# dintervalometer.net
KiCad netlist of a schematic drawn in EAGLE
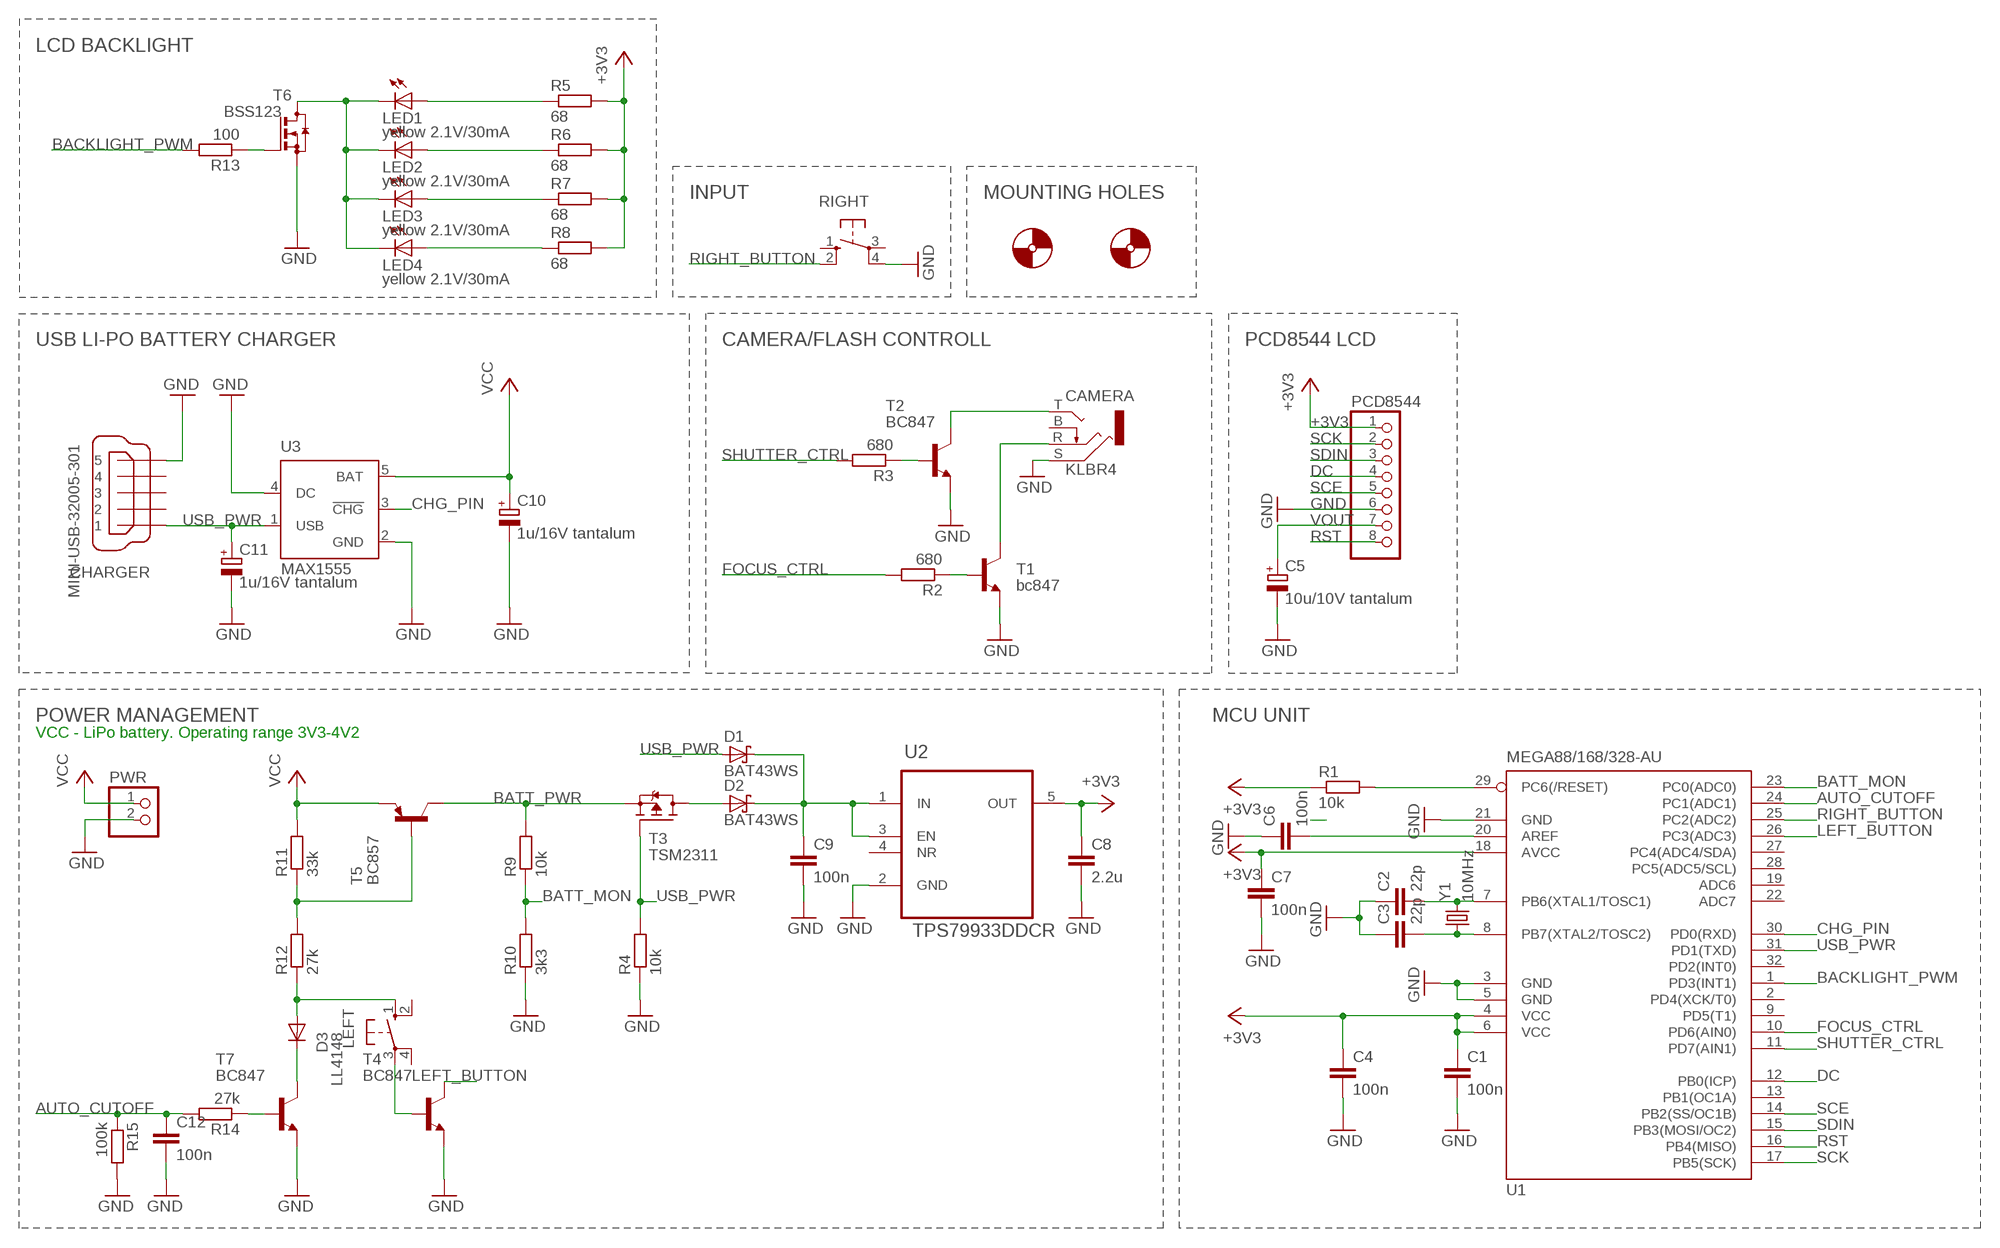
[diagram p0: schematic, sheet 1]

(export (version "E")
  (design (tool "Eeschema 10.0.6"))
  (components
    (comp (ref "C1")
      (value "100n")
      (footprint "eagle-import:C0805")
      (libsource (lib "eagle-import") (part "C-EUC0805"))
    )
    (comp (ref "C2")
      (value "22p")
      (footprint "eagle-import:C0805")
      (libsource (lib "eagle-import") (part "C-EUC0805"))
    )
    (comp (ref "C3")
      (value "22p")
      (footprint "eagle-import:C0805")
      (libsource (lib "eagle-import") (part "C-EUC0805"))
    )
    (comp (ref "C4")
      (value "100n")
      (footprint "eagle-import:C0805")
      (libsource (lib "eagle-import") (part "C-EUC0805"))
    )
    (comp (ref "C5")
      (value "10u/10V tantalum")
      (footprint "eagle-import:SMC_A")
      (libsource (lib "eagle-import") (part "CPOL-EUSMCA"))
    )
    (comp (ref "C6")
      (value "100n")
      (footprint "eagle-import:C0805")
      (libsource (lib "eagle-import") (part "C-EUC0805"))
    )
    (comp (ref "C7")
      (value "100n")
      (footprint "eagle-import:C0805")
      (libsource (lib "eagle-import") (part "C-EUC0805"))
    )
    (comp (ref "C8")
      (value "2.2u")
      (footprint "eagle-import:C0805")
      (libsource (lib "eagle-import") (part "C-EUC0805"))
    )
    (comp (ref "C9")
      (value "100n")
      (footprint "eagle-import:C0805")
      (libsource (lib "eagle-import") (part "C-EUC0805"))
    )
    (comp (ref "C10")
      (value "1u/16V tantalum")
      (footprint "eagle-import:SMC_A")
      (libsource (lib "eagle-import") (part "CPOL-EUSMCA"))
    )
    (comp (ref "C11")
      (value "1u/16V tantalum")
      (footprint "eagle-import:SMC_A")
      (libsource (lib "eagle-import") (part "CPOL-EUSMCA"))
    )
    (comp (ref "C12")
      (value "100n")
      (footprint "eagle-import:C0805")
      (libsource (lib "eagle-import") (part "C-EUC0805"))
    )
    (comp (ref "CAMERA")
      (value "KLBR4")
      (footprint "eagle-import:KLBR4")
      (fields (field (name "MPN") "KLBR 4"))
      (libsource (lib "eagle-import") (part "KLBR4"))
    )
    (comp (ref "CHARGER")
      (value "MINI-USB-32005-301")
      (footprint "eagle-import:32005-301")
      (libsource (lib "eagle-import") (part "MINI-USB-32005-301"))
    )
    (comp (ref "D1")
      (value "BAT43WS")
      (footprint "eagle-import:SOD323_ST")
      (libsource (lib "eagle-import") (part "BAT43WS"))
    )
    (comp (ref "D2")
      (value "BAT43WS")
      (footprint "eagle-import:SOD323_ST")
      (libsource (lib "eagle-import") (part "BAT43WS"))
    )
    (comp (ref "D3")
      (value "LL4148")
      (footprint "eagle-import:SOD80C")
      (libsource (lib "eagle-import") (part "DIODE-SOD80C"))
    )
    (comp (ref "LED1")
      (value "yellow 2.1V/30mA")
      (footprint "eagle-import:CHIP-LED0805")
      (libsource (lib "eagle-import") (part "LEDCHIP-LED0805"))
    )
    (comp (ref "LED2")
      (value "yellow 2.1V/30mA")
      (footprint "eagle-import:CHIP-LED0805")
      (libsource (lib "eagle-import") (part "LEDCHIP-LED0805"))
    )
    (comp (ref "LED3")
      (value "yellow 2.1V/30mA")
      (footprint "eagle-import:CHIP-LED0805")
      (libsource (lib "eagle-import") (part "LEDCHIP-LED0805"))
    )
    (comp (ref "LED4")
      (value "yellow 2.1V/30mA")
      (footprint "eagle-import:CHIP-LED0805")
      (libsource (lib "eagle-import") (part "LEDCHIP-LED0805"))
    )
    (comp (ref "LEFT")
      (value "10-XX")
      (footprint "eagle-import:B3F-10XX")
      (fields (field (name "MPN") "B3F-1000"))
      (libsource (lib "eagle-import") (part "10-XX"))
    )
    (comp (ref "PCD8544")
      (value "PINHD-1X8")
      (footprint "eagle-import:1X08")
      (libsource (lib "eagle-import") (part "PINHD-1X8"))
    )
    (comp (ref "PWR")
      (value "PINHD-1X2/90")
      (footprint "eagle-import:1X02_90")
      (libsource (lib "eagle-import") (part "PINHD-1X2/90"))
    )
    (comp (ref "R1")
      (value "10k")
      (footprint "eagle-import:M0805")
      (libsource (lib "eagle-import") (part "R-EU_M0805"))
    )
    (comp (ref "R2")
      (value "680")
      (footprint "eagle-import:M0805")
      (libsource (lib "eagle-import") (part "R-EU_M0805"))
    )
    (comp (ref "R3")
      (value "680")
      (footprint "eagle-import:M0805")
      (libsource (lib "eagle-import") (part "R-EU_M0805"))
    )
    (comp (ref "R4")
      (value "10k")
      (footprint "eagle-import:M0805")
      (libsource (lib "eagle-import") (part "R-EU_M0805"))
    )
    (comp (ref "R5")
      (value "68")
      (footprint "eagle-import:M0805")
      (libsource (lib "eagle-import") (part "R-EU_M0805"))
    )
    (comp (ref "R6")
      (value "68")
      (footprint "eagle-import:M0805")
      (libsource (lib "eagle-import") (part "R-EU_M0805"))
    )
    (comp (ref "R7")
      (value "68")
      (footprint "eagle-import:M0805")
      (libsource (lib "eagle-import") (part "R-EU_M0805"))
    )
    (comp (ref "R8")
      (value "68")
      (footprint "eagle-import:M0805")
      (libsource (lib "eagle-import") (part "R-EU_M0805"))
    )
    (comp (ref "R9")
      (value "10k")
      (footprint "eagle-import:M0805")
      (libsource (lib "eagle-import") (part "R-EU_M0805"))
    )
    (comp (ref "R10")
      (value "3k3")
      (footprint "eagle-import:M0805")
      (libsource (lib "eagle-import") (part "R-EU_M0805"))
    )
    (comp (ref "R11")
      (value "33k")
      (footprint "eagle-import:M0805")
      (libsource (lib "eagle-import") (part "R-EU_M0805"))
    )
    (comp (ref "R12")
      (value "27k")
      (footprint "eagle-import:M0805")
      (libsource (lib "eagle-import") (part "R-EU_M0805"))
    )
    (comp (ref "R13")
      (value "100")
      (footprint "eagle-import:M0805")
      (libsource (lib "eagle-import") (part "R-EU_M0805"))
    )
    (comp (ref "R14")
      (value "27k")
      (footprint "eagle-import:M0805")
      (libsource (lib "eagle-import") (part "R-EU_M0805"))
    )
    (comp (ref "R15")
      (value "100k")
      (footprint "eagle-import:M0805")
      (libsource (lib "eagle-import") (part "R-EU_M0805"))
    )
    (comp (ref "RIGHT")
      (value "10-XX")
      (footprint "eagle-import:B3F-10XX")
      (fields
        (field (name "MPN") "B3F-1000")
        (field (name "MPN_1") "B3F-1000")
        (field (name "OC_FARNELL") "176432")
        (field (name "OC_NEWARK") "36M3542")
      )
      (libsource (lib "eagle-import") (part "10-XX"))
    )
    (comp (ref "T1")
      (value "bc847")
      (footprint "eagle-import:SOT23-BEC")
      (libsource (lib "eagle-import") (part "-NPN-SOT23-BECBC847"))
    )
    (comp (ref "T2")
      (value "BC847")
      (footprint "eagle-import:SOT23-BEC")
      (libsource (lib "eagle-import") (part "-NPN-SOT23-BECBC847"))
    )
    (comp (ref "T3")
      (value "TSM2311")
      (footprint "eagle-import:SOT23")
      (libsource (lib "eagle-import") (part "TSM2311"))
    )
    (comp (ref "T4")
      (value "BC847")
      (footprint "eagle-import:SOT23")
      (libsource (lib "eagle-import") (part "BC847"))
    )
    (comp (ref "T5")
      (value "BC857")
      (footprint "eagle-import:SOT23-BEC")
      (libsource (lib "eagle-import") (part "-PNP-SOT23-BECBC857A"))
    )
    (comp (ref "T6")
      (value "BSS123")
      (footprint "eagle-import:SOT23")
      (libsource (lib "eagle-import") (part "BSS123"))
    )
    (comp (ref "T7")
      (value "BC847")
      (footprint "eagle-import:SOT23")
      (libsource (lib "eagle-import") (part "BC847"))
    )
    (comp (ref "U1")
      (value "MEGA88/168/328-AU")
      (footprint "eagle-import:TQFP32-08")
      (fields (field (name "MPN") "ATMEGA8-16AU"))
      (libsource (lib "eagle-import") (part "MEGA8-AI"))
    )
    (comp (ref "U2")
      (value "TPS79933DDCR")
      (footprint "eagle-import:SOT95P290X145-5N")
      (fields (field (name "MPN") "TPS73033DBVT"))
      (libsource (lib "eagle-import") (part "TPS73033DBVT"))
    )
    (comp (ref "U3")
      (value "MAX1555")
      (footprint "eagle-import:SOT23-5L")
      (fields (field (name "MF") "MAXIM") (field (name "MPN") "MAX1555EZK+T"))
      (libsource (lib "eagle-import") (part "MAX1555"))
    )
    (comp (ref "X1")
      (value "2.8MM_HOLE")
      (footprint "eagle-import:2.8MM_HOLE")
      (libsource (lib "eagle-import") (part "2.8MM_HOLE"))
    )
    (comp (ref "X3")
      (value "2.8MM_HOLE")
      (footprint "eagle-import:2.8MM_HOLE")
      (libsource (lib "eagle-import") (part "2.8MM_HOLE"))
    )
    (comp (ref "Y1")
      (value "10MHz")
      (footprint "eagle-import:5X3.2MM")
      (libsource (lib "eagle-import") (part "CRYSTAL"))
    )
  )
  (nets
    (net (code "1") (name "+3V3") (class "Default")
      (node (ref "C1") (pin "1") (pinfunction "1_1") (pintype "passive"))
      (node (ref "C4") (pin "1") (pinfunction "1_1") (pintype "passive"))
      (node (ref "C7") (pin "1") (pinfunction "1_1") (pintype "passive"))
      (node (ref "C8") (pin "1") (pinfunction "1_1") (pintype "passive"))
      (node (ref "PCD8544") (pin "1") (pinfunction "1_1") (pintype "passive"))
      (node (ref "R1") (pin "1") (pinfunction "1_1") (pintype "passive"))
      (node (ref "R5") (pin "2") (pinfunction "2_2") (pintype "passive"))
      (node (ref "R6") (pin "2") (pinfunction "2_2") (pintype "passive"))
      (node (ref "R7") (pin "2") (pinfunction "2_2") (pintype "passive"))
      (node (ref "R8") (pin "2") (pinfunction "2_2") (pintype "passive"))
      (node (ref "U1") (pin "18") (pinfunction "AVCC_18") (pintype "power_in"))
      (node (ref "U1") (pin "4") (pinfunction "VCC_4") (pintype "power_in"))
      (node (ref "U1") (pin "6") (pinfunction "VCC_6") (pintype "power_in"))
      (node (ref "U2") (pin "5") (pinfunction "OUT_5") (pintype "output"))
    )
    (net (code "2") (name "/AUTO_CUTOFF") (class "Default")
      (node (ref "C12") (pin "1") (pinfunction "1_1") (pintype "passive"))
      (node (ref "R14") (pin "2") (pinfunction "2_2") (pintype "passive"))
      (node (ref "R15") (pin "1") (pinfunction "1_1") (pintype "passive"))
      (node (ref "U1") (pin "24") (pinfunction "PC1(ADC1)_24") (pintype "bidirectional"))
    )
    (net (code "3") (name "/BACKLIGHT_PWM") (class "Default")
      (node (ref "R13") (pin "2") (pinfunction "2_2") (pintype "passive"))
      (node (ref "U1") (pin "1") (pinfunction "PD3(INT1)_1") (pintype "bidirectional"))
    )
    (net (code "4") (name "/BATT_MON") (class "Default")
      (node (ref "R10") (pin "2") (pinfunction "2_2") (pintype "passive"))
      (node (ref "R9") (pin "1") (pinfunction "1_1") (pintype "passive"))
      (node (ref "U1") (pin "23") (pinfunction "PC0(ADC0)_23") (pintype "bidirectional"))
    )
    (net (code "5") (name "/BATT_PWR") (class "Default")
      (node (ref "R9") (pin "2") (pinfunction "2_2") (pintype "passive"))
      (node (ref "T3") (pin "2") (pinfunction "S_2") (pintype "passive"))
      (node (ref "T5") (pin "C") (pinfunction "C_C") (pintype "passive"))
    )
    (net (code "6") (name "/CHG_PIN") (class "Default")
      (node (ref "U1") (pin "30") (pinfunction "PD0(RXD)_30") (pintype "bidirectional"))
      (node (ref "U3") (pin "3") (pinfunction "~{CHG}_3") (pintype "output"))
    )
    (net (code "7") (name "/DC") (class "Default")
      (node (ref "PCD8544") (pin "4") (pinfunction "4_4") (pintype "passive"))
      (node (ref "U1") (pin "12") (pinfunction "PB0(ICP)_12") (pintype "bidirectional"))
    )
    (net (code "8") (name "/FOCUS_CTRL") (class "Default")
      (node (ref "R2") (pin "2") (pinfunction "2_2") (pintype "passive"))
      (node (ref "U1") (pin "10") (pinfunction "PD6(AIN0)_10") (pintype "bidirectional"))
    )
    (net (code "9") (name "/LEFT_BUTTON") (class "Default")
      (node (ref "T4") (pin "3") (pinfunction "C_3") (pintype "passive"))
      (node (ref "U1") (pin "26") (pinfunction "PC3(ADC3)_26") (pintype "bidirectional"))
    )
    (net (code "10") (name "/RIGHT_BUTTON") (class "Default")
      (node (ref "RIGHT") (pin "2") (pinfunction "S1_2") (pintype "passive"))
      (node (ref "U1") (pin "25") (pinfunction "PC2(ADC2)_25") (pintype "bidirectional"))
    )
    (net (code "11") (name "/RST") (class "Default")
      (node (ref "PCD8544") (pin "8") (pinfunction "8_8") (pintype "passive"))
      (node (ref "U1") (pin "16") (pinfunction "PB4(MISO)_16") (pintype "bidirectional"))
    )
    (net (code "12") (name "/SCE") (class "Default")
      (node (ref "PCD8544") (pin "5") (pinfunction "5_5") (pintype "passive"))
      (node (ref "U1") (pin "14") (pinfunction "PB2(SS/OC1B)_14") (pintype "bidirectional"))
    )
    (net (code "13") (name "/SCK") (class "Default")
      (node (ref "PCD8544") (pin "2") (pinfunction "2_2") (pintype "passive"))
      (node (ref "U1") (pin "17") (pinfunction "PB5(SCK)_17") (pintype "bidirectional"))
    )
    (net (code "14") (name "/SDIN") (class "Default")
      (node (ref "PCD8544") (pin "3") (pinfunction "3_3") (pintype "passive"))
      (node (ref "U1") (pin "15") (pinfunction "PB3(MOSI/OC2)_15") (pintype "bidirectional"))
    )
    (net (code "15") (name "/SHUTTER_CTRL") (class "Default")
      (node (ref "R3") (pin "2") (pinfunction "2_2") (pintype "passive"))
      (node (ref "U1") (pin "11") (pinfunction "PD7(AIN1)_11") (pintype "bidirectional"))
    )
    (net (code "16") (name "/USB_PWR") (class "Default")
      (node (ref "C11") (pin "+") (pinfunction "+_+") (pintype "passive"))
      (node (ref "CHARGER") (pin "1") (pinfunction "1_1") (pintype "passive"))
      (node (ref "D1") (pin "A") (pinfunction "A_A") (pintype "passive"))
      (node (ref "R4") (pin "2") (pinfunction "2_2") (pintype "passive"))
      (node (ref "T3") (pin "1") (pinfunction "G_1") (pintype "passive"))
      (node (ref "U1") (pin "31") (pinfunction "PD1(TXD)_31") (pintype "bidirectional"))
      (node (ref "U3") (pin "1") (pinfunction "USB_1") (pintype "input"))
    )
    (net (code "17") (name "/VOUT") (class "Default")
      (node (ref "C5") (pin "+") (pinfunction "+_+") (pintype "passive"))
      (node (ref "PCD8544") (pin "7") (pinfunction "7_7") (pintype "passive"))
    )
    (net (code "18") (name "GND") (class "Default")
      (node (ref "C1") (pin "2") (pinfunction "2_2") (pintype "passive"))
      (node (ref "C10") (pin "-") (pinfunction "-_-") (pintype "passive"))
      (node (ref "C11") (pin "-") (pinfunction "-_-") (pintype "passive"))
      (node (ref "C12") (pin "2") (pinfunction "2_2") (pintype "passive"))
      (node (ref "C2") (pin "1") (pinfunction "1_1") (pintype "passive"))
      (node (ref "C3") (pin "1") (pinfunction "1_1") (pintype "passive"))
      (node (ref "C4") (pin "2") (pinfunction "2_2") (pintype "passive"))
      (node (ref "C5") (pin "-") (pinfunction "-_-") (pintype "passive"))
      (node (ref "C6") (pin "1") (pinfunction "1_1") (pintype "passive"))
      (node (ref "C7") (pin "2") (pinfunction "2_2") (pintype "passive"))
      (node (ref "C8") (pin "2") (pinfunction "2_2") (pintype "passive"))
      (node (ref "C9") (pin "2") (pinfunction "2_2") (pintype "passive"))
      (node (ref "CAMERA") (pin "S") (pinfunction "S_S") (pintype "passive"))
      (node (ref "CHARGER") (pin "5") (pinfunction "5_5") (pintype "passive"))
      (node (ref "PCD8544") (pin "6") (pinfunction "6_6") (pintype "passive"))
      (node (ref "PWR") (pin "2") (pinfunction "2_2") (pintype "passive"))
      (node (ref "R10") (pin "1") (pinfunction "1_1") (pintype "passive"))
      (node (ref "R15") (pin "2") (pinfunction "2_2") (pintype "passive"))
      (node (ref "R4") (pin "1") (pinfunction "1_1") (pintype "passive"))
      (node (ref "RIGHT") (pin "4") (pinfunction "P1_4") (pintype "passive"))
      (node (ref "T1") (pin "E") (pinfunction "E_E") (pintype "passive"))
      (node (ref "T2") (pin "E") (pinfunction "E_E") (pintype "passive"))
      (node (ref "T4") (pin "2") (pinfunction "E_2") (pintype "passive"))
      (node (ref "T6") (pin "2") (pinfunction "S_2") (pintype "passive"))
      (node (ref "T7") (pin "2") (pinfunction "E_2") (pintype "passive"))
      (node (ref "U1") (pin "21") (pinfunction "GND_21") (pintype "power_in"))
      (node (ref "U1") (pin "3") (pinfunction "GND_3") (pintype "power_in"))
      (node (ref "U1") (pin "5") (pinfunction "GND_5") (pintype "power_in"))
      (node (ref "U2") (pin "2") (pinfunction "GND_2") (pintype "passive"))
      (node (ref "U3") (pin "2") (pinfunction "GND_2") (pintype "power_in"))
      (node (ref "U3") (pin "4") (pinfunction "DC_4") (pintype "input"))
    )
    (net (code "19") (name "Net-(CAMERA-PadR)") (class "Default")
      (node (ref "CAMERA") (pin "R") (pinfunction "R_R") (pintype "passive"))
      (node (ref "T1") (pin "C") (pinfunction "C_C") (pintype "passive"))
    )
    (net (code "20") (name "Net-(CAMERA-PadT)") (class "Default")
      (node (ref "CAMERA") (pin "T") (pinfunction "T_T") (pintype "passive"))
      (node (ref "T2") (pin "C") (pinfunction "C_C") (pintype "passive"))
    )
    (net (code "21") (name "Net-(LED1-PadA)") (class "Default")
      (node (ref "LED1") (pin "A") (pinfunction "A_A") (pintype "passive"))
      (node (ref "R5") (pin "1") (pinfunction "1_1") (pintype "passive"))
    )
    (net (code "22") (name "Net-(LED2-PadA)") (class "Default")
      (node (ref "LED2") (pin "A") (pinfunction "A_A") (pintype "passive"))
      (node (ref "R6") (pin "1") (pinfunction "1_1") (pintype "passive"))
    )
    (net (code "23") (name "Net-(LED3-PadA)") (class "Default")
      (node (ref "LED3") (pin "A") (pinfunction "A_A") (pintype "passive"))
      (node (ref "R7") (pin "1") (pinfunction "1_1") (pintype "passive"))
    )
    (net (code "24") (name "Net-(LED4-PadA)") (class "Default")
      (node (ref "LED4") (pin "A") (pinfunction "A_A") (pintype "passive"))
      (node (ref "R8") (pin "1") (pinfunction "1_1") (pintype "passive"))
    )
    (net (code "25") (name "Net-(LEFT-P)") (class "Default")
      (node (ref "LEFT") (pin "3") (pinfunction "P_3") (pintype "passive"))
      (node (ref "T4") (pin "1") (pinfunction "B_1") (pintype "passive"))
    )
    (net (code "26") (name "Net-(LEFT-S)") (class "Default")
      (node (ref "D3") (pin "A") (pinfunction "A_A") (pintype "passive"))
      (node (ref "LEFT") (pin "1") (pinfunction "S_1") (pintype "passive"))
      (node (ref "R12") (pin "1") (pinfunction "1_1") (pintype "passive"))
    )
    (net (code "27") (name "Net-(R2-Pad1)") (class "Default")
      (node (ref "R2") (pin "1") (pinfunction "1_1") (pintype "passive"))
      (node (ref "T1") (pin "B") (pinfunction "B_B") (pintype "passive"))
    )
    (net (code "28") (name "Net-(R3-Pad1)") (class "Default")
      (node (ref "R3") (pin "1") (pinfunction "1_1") (pintype "passive"))
      (node (ref "T2") (pin "B") (pinfunction "B_B") (pintype "passive"))
    )
    (net (code "29") (name "Net-(R11-Pad1)") (class "Default")
      (node (ref "R11") (pin "1") (pinfunction "1_1") (pintype "passive"))
      (node (ref "R12") (pin "2") (pinfunction "2_2") (pintype "passive"))
      (node (ref "T5") (pin "B") (pinfunction "B_B") (pintype "passive"))
    )
    (net (code "30") (name "Net-(T3-D)") (class "Default")
      (node (ref "D2") (pin "A") (pinfunction "A_A") (pintype "passive"))
      (node (ref "T3") (pin "3") (pinfunction "D_3") (pintype "passive"))
    )
    (net (code "31") (name "Net-(T6-D)") (class "Default")
      (node (ref "LED1") (pin "C") (pinfunction "C_C") (pintype "passive"))
      (node (ref "LED2") (pin "C") (pinfunction "C_C") (pintype "passive"))
      (node (ref "LED3") (pin "C") (pinfunction "C_C") (pintype "passive"))
      (node (ref "LED4") (pin "C") (pinfunction "C_C") (pintype "passive"))
      (node (ref "T6") (pin "3") (pinfunction "D_3") (pintype "passive"))
    )
    (net (code "32") (name "Net-(T6-G)") (class "Default")
      (node (ref "R13") (pin "1") (pinfunction "1_1") (pintype "passive"))
      (node (ref "T6") (pin "1") (pinfunction "G_1") (pintype "passive"))
    )
    (net (code "33") (name "Net-(T7-B)") (class "Default")
      (node (ref "R14") (pin "1") (pinfunction "1_1") (pintype "passive"))
      (node (ref "T7") (pin "1") (pinfunction "B_1") (pintype "passive"))
    )
    (net (code "34") (name "Net-(T7-C)") (class "Default")
      (node (ref "D3") (pin "C") (pinfunction "C_C") (pintype "passive"))
      (node (ref "T7") (pin "3") (pinfunction "C_3") (pintype "passive"))
    )
    (net (code "35") (name "Net-(U1-AREF)") (class "Default")
      (node (ref "C6") (pin "2") (pinfunction "2_2") (pintype "passive"))
      (node (ref "U1") (pin "20") (pinfunction "AREF_20") (pintype "passive"))
    )
    (net (code "36") (name "Net-(U1-PB6(XTAL1{slash}TOSC1))") (class "Default")
      (node (ref "C2") (pin "2") (pinfunction "2_2") (pintype "passive"))
      (node (ref "U1") (pin "7") (pinfunction "PB6(XTAL1/TOSC1)_7") (pintype "bidirectional"))
      (node (ref "Y1") (pin "3") (pinfunction "2_3") (pintype "passive"))
    )
    (net (code "37") (name "Net-(U1-PB7(XTAL2{slash}TOSC2))") (class "Default")
      (node (ref "C3") (pin "2") (pinfunction "2_2") (pintype "passive"))
      (node (ref "U1") (pin "8") (pinfunction "PB7(XTAL2/TOSC2)_8") (pintype "bidirectional"))
      (node (ref "Y1") (pin "1") (pinfunction "1_1") (pintype "passive"))
    )
    (net (code "38") (name "Net-(U1-PC6({slash}RESET))") (class "Default")
      (node (ref "R1") (pin "2") (pinfunction "2_2") (pintype "passive"))
      (node (ref "U1") (pin "29") (pinfunction "PC6(/RESET)_29") (pintype "bidirectional"))
    )
    (net (code "39") (name "Net-(U2-EN)") (class "Default")
      (node (ref "C9") (pin "1") (pinfunction "1_1") (pintype "passive"))
      (node (ref "D1") (pin "C") (pinfunction "C_C") (pintype "passive"))
      (node (ref "D2") (pin "C") (pinfunction "C_C") (pintype "passive"))
      (node (ref "U2") (pin "1") (pinfunction "IN_1") (pintype "input"))
      (node (ref "U2") (pin "3") (pinfunction "EN_3") (pintype "input"))
    )
    (net (code "40") (name "VCC") (class "Default")
      (node (ref "C10") (pin "+") (pinfunction "+_+") (pintype "passive"))
      (node (ref "PWR") (pin "1") (pinfunction "1_1") (pintype "passive"))
      (node (ref "R11") (pin "2") (pinfunction "2_2") (pintype "passive"))
      (node (ref "T5") (pin "E") (pinfunction "E_E") (pintype "passive"))
      (node (ref "U3") (pin "5") (pinfunction "BAT_5") (pintype "passive"))
    )
    (net (code "41") (name "unconnected-(CAMERA-PadB)") (class "Default")
      (node (ref "CAMERA") (pin "B") (pinfunction "B_B") (pintype "passive"))
    )
    (net (code "42") (name "unconnected-(CHARGER-Pad2)") (class "Default")
      (node (ref "CHARGER") (pin "2") (pinfunction "2_2") (pintype "passive"))
    )
    (net (code "43") (name "unconnected-(CHARGER-Pad3)") (class "Default")
      (node (ref "CHARGER") (pin "3") (pinfunction "3_3") (pintype "passive"))
    )
    (net (code "44") (name "unconnected-(CHARGER-Pad4)") (class "Default")
      (node (ref "CHARGER") (pin "4") (pinfunction "4_4") (pintype "passive"))
    )
    (net (code "45") (name "unconnected-(LEFT-P1-Pad4)") (class "Default")
      (node (ref "LEFT") (pin "4") (pinfunction "P1_4") (pintype "passive"))
    )
    (net (code "46") (name "unconnected-(LEFT-S1-Pad2)") (class "Default")
      (node (ref "LEFT") (pin "2") (pinfunction "S1_2") (pintype "passive"))
    )
    (net (code "47") (name "unconnected-(RIGHT-P-Pad3)") (class "Default")
      (node (ref "RIGHT") (pin "3") (pinfunction "P_3") (pintype "passive"))
    )
    (net (code "48") (name "unconnected-(RIGHT-S-Pad1)") (class "Default")
      (node (ref "RIGHT") (pin "1") (pinfunction "S_1") (pintype "passive"))
    )
    (net (code "49") (name "unconnected-(U1-ADC6-Pad19)") (class "Default")
      (node (ref "U1") (pin "19") (pinfunction "ADC6_19") (pintype "bidirectional"))
    )
    (net (code "50") (name "unconnected-(U1-ADC7-Pad22)") (class "Default")
      (node (ref "U1") (pin "22") (pinfunction "ADC7_22") (pintype "bidirectional"))
    )
    (net (code "51") (name "unconnected-(U1-PB1(OC1A)-Pad13)") (class "Default")
      (node (ref "U1") (pin "13") (pinfunction "PB1(OC1A)_13") (pintype "bidirectional"))
    )
    (net (code "52") (name "unconnected-(U1-PC4(ADC4{slash}SDA)-Pad27)") (class "Default")
      (node (ref "U1") (pin "27") (pinfunction "PC4(ADC4/SDA)_27") (pintype "bidirectional"))
    )
    (net (code "53") (name "unconnected-(U1-PC5(ADC5{slash}SCL)-Pad28)") (class "Default")
      (node (ref "U1") (pin "28") (pinfunction "PC5(ADC5/SCL)_28") (pintype "bidirectional"))
    )
    (net (code "54") (name "unconnected-(U1-PD2(INT0)-Pad32)") (class "Default")
      (node (ref "U1") (pin "32") (pinfunction "PD2(INT0)_32") (pintype "bidirectional"))
    )
    (net (code "55") (name "unconnected-(U1-PD4(XCK{slash}T0)-Pad2)") (class "Default")
      (node (ref "U1") (pin "2") (pinfunction "PD4(XCK/T0)_2") (pintype "bidirectional"))
    )
    (net (code "56") (name "unconnected-(U1-PD5(T1)-Pad9)") (class "Default")
      (node (ref "U1") (pin "9") (pinfunction "PD5(T1)_9") (pintype "bidirectional"))
    )
    (net (code "57") (name "unconnected-(U2-NR-Pad4)") (class "Default")
      (node (ref "U2") (pin "4") (pinfunction "NR_4") (pintype "input"))
    )
  )
)
